# POC-save.net
KiCad netlist of a schematic drawn in EAGLE
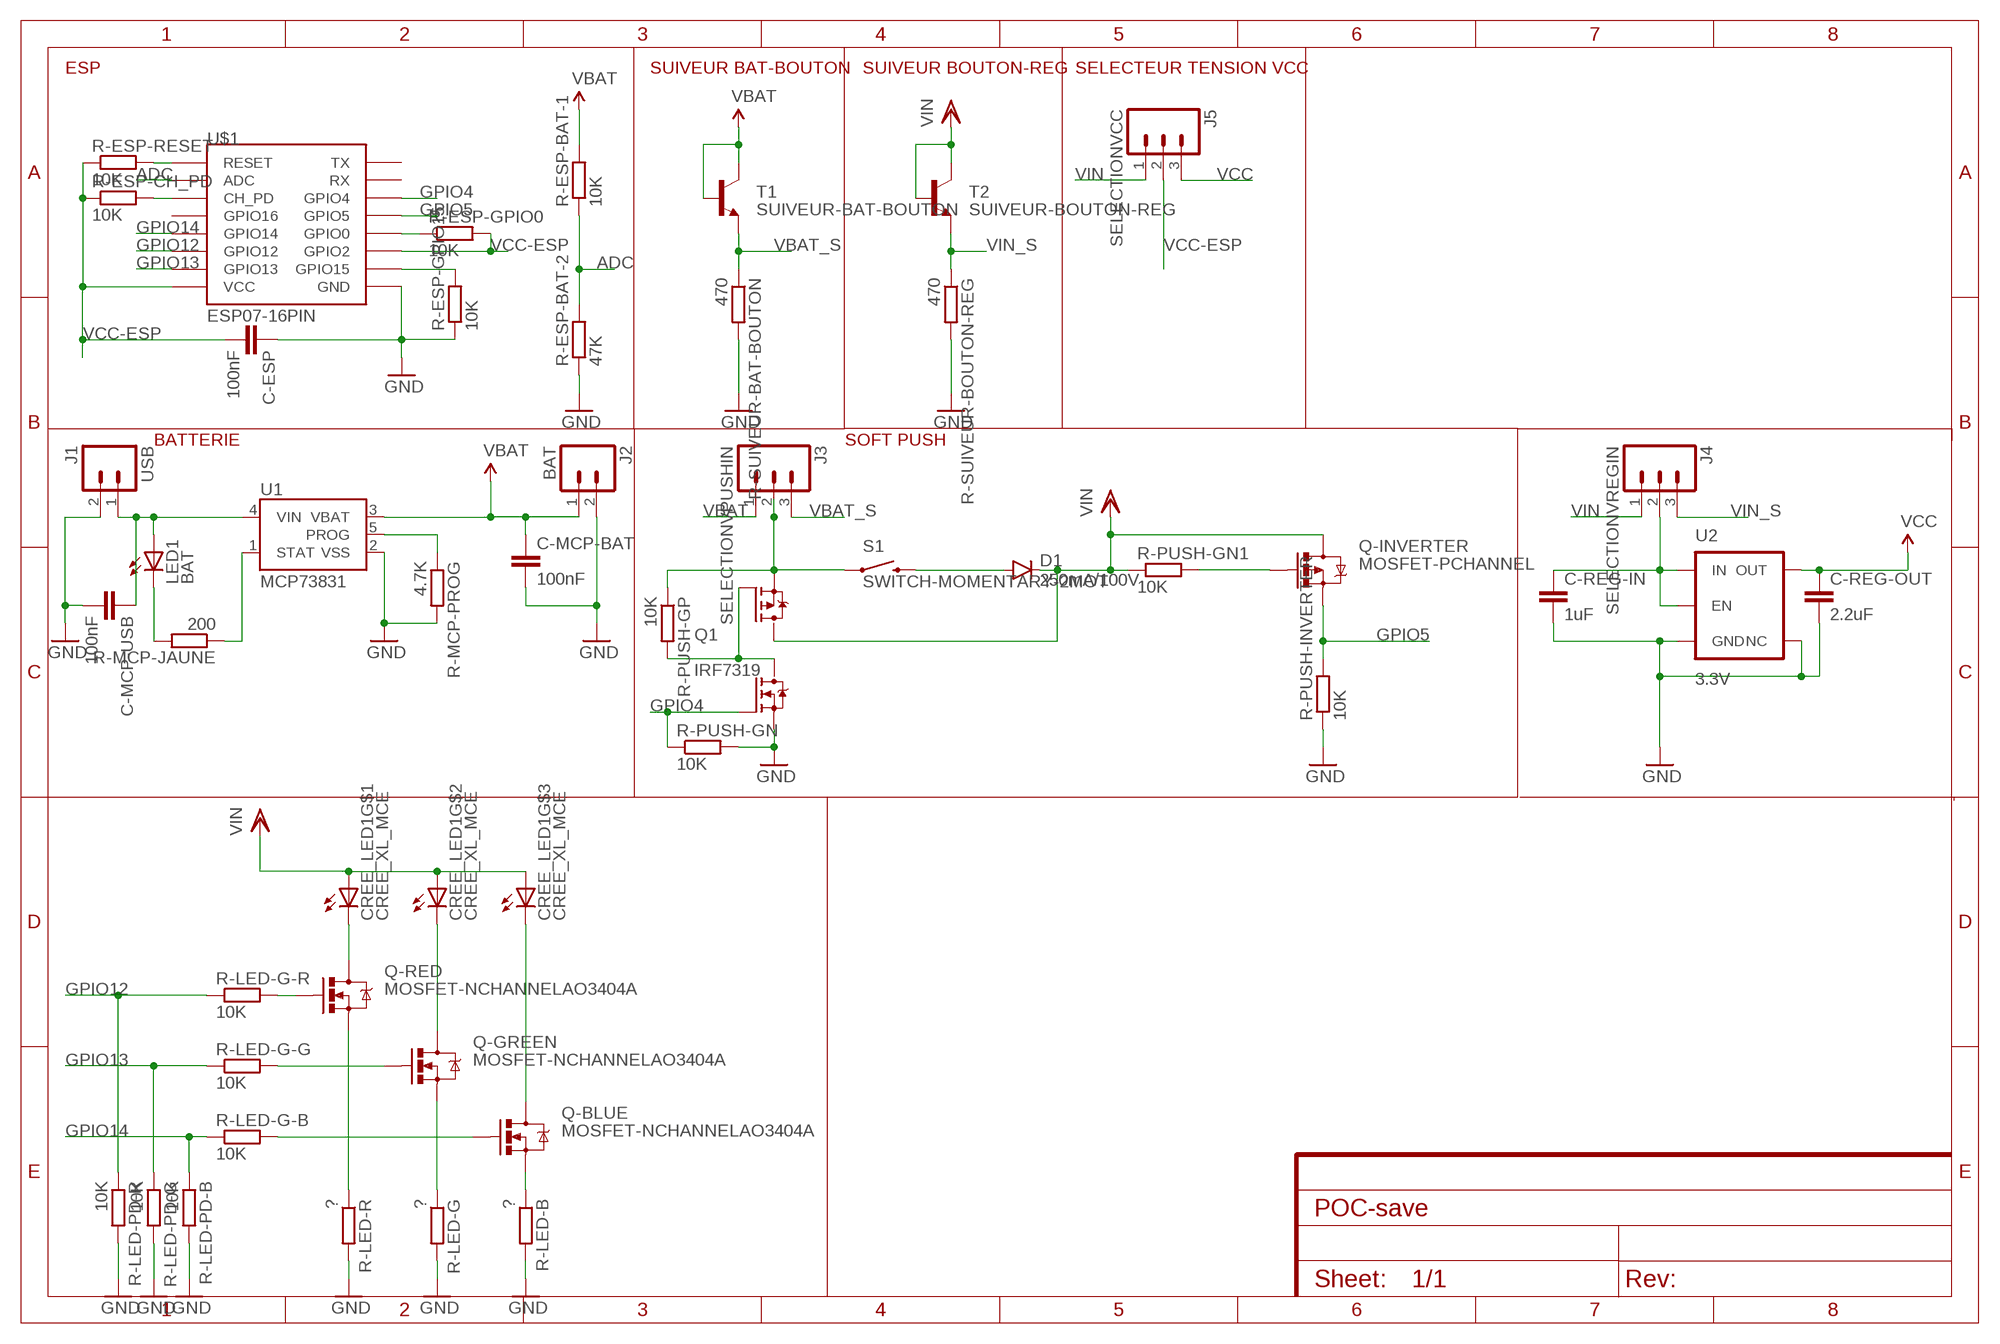
[diagram p0: schematic, sheet 1]

(export (version "E")
  (design (tool "Eeschema 10.0.6"))
  (components
    (comp (ref "C-ESP")
      (value "100nF")
      (footprint "eagle-import:C0805")
      (libsource (lib "eagle-import") (part "C-EUC0805"))
    )
    (comp (ref "C-MCP-BAT")
      (value "100nF")
      (footprint "eagle-import:C0805")
      (libsource (lib "eagle-import") (part "C-EUC0805"))
    )
    (comp (ref "C-MCP-USB")
      (value "100nF")
      (footprint "eagle-import:C0805")
      (libsource (lib "eagle-import") (part "C-EUC0805"))
    )
    (comp (ref "C-REG-IN")
      (value "1uF")
      (footprint "eagle-import:C0805")
      (libsource (lib "eagle-import") (part "C-EUC0805"))
    )
    (comp (ref "C-REG-OUT")
      (value "2.2uF")
      (footprint "eagle-import:C0805")
      (libsource (lib "eagle-import") (part "C-EUC0805"))
    )
    (comp (ref "CREE_LED1")
      (value "CREE_XL_MCE")
      (footprint "eagle-import:CREE_XL_MCE")
      (libsource (lib "eagle-import") (part "CREE_XL_MCE"))
    )
    (comp (ref "D1")
      (value "250mA/100V")
      (footprint "eagle-import:SOD-323")
      (libsource (lib "eagle-import") (part "DIODEBAS16"))
    )
    (comp (ref "J1")
      (value "USB")
      (footprint "eagle-import:1X02")
      (libsource (lib "eagle-import") (part "M02PTH"))
    )
    (comp (ref "J2")
      (value "BAT")
      (footprint "eagle-import:1X02")
      (libsource (lib "eagle-import") (part "M02PTH"))
    )
    (comp (ref "J3")
      (value "SELECTIONVPUSHIN")
      (footprint "eagle-import:1X03")
      (libsource (lib "eagle-import") (part "M03PTH"))
    )
    (comp (ref "J4")
      (value "SELECTIONVREGIN")
      (footprint "eagle-import:1X03")
      (libsource (lib "eagle-import") (part "M03PTH"))
    )
    (comp (ref "J5")
      (value "SELECTIONVCC")
      (footprint "eagle-import:1X03")
      (libsource (lib "eagle-import") (part "M03PTH"))
    )
    (comp (ref "LED1")
      (value "BAT")
      (footprint "eagle-import:CHIPLED_0805")
      (libsource (lib "eagle-import") (part "LEDCHIPLED_0805"))
    )
    (comp (ref "Q-BLUE")
      (value "MOSFET-NCHANNELAO3404A")
      (footprint "eagle-import:SOT23-3")
      (libsource (lib "eagle-import") (part "MOSFET-NCHANNELAO3404A"))
    )
    (comp (ref "Q-GREEN")
      (value "MOSFET-NCHANNELAO3404A")
      (footprint "eagle-import:SOT23-3")
      (libsource (lib "eagle-import") (part "MOSFET-NCHANNELAO3404A"))
    )
    (comp (ref "Q-INVERTER")
      (value "MOSFET-PCHANNEL")
      (footprint "eagle-import:SOT23-3")
      (libsource (lib "eagle-import") (part "MOSFET-PCHANNEL"))
    )
    (comp (ref "Q-RED")
      (value "MOSFET-NCHANNELAO3404A")
      (footprint "eagle-import:SOT23-3")
      (libsource (lib "eagle-import") (part "MOSFET-NCHANNELAO3404A"))
    )
    (comp (ref "Q1")
      (value "IRF7319")
      (footprint "eagle-import:SO08-IRF")
      (libsource (lib "eagle-import") (part "IRF7319"))
    )
    (comp (ref "R-ESP-BAT-1")
      (value "10K")
      (footprint "eagle-import:M0805")
      (libsource (lib "eagle-import") (part "R-EU_M0805"))
    )
    (comp (ref "R-ESP-BAT-2")
      (value "47K")
      (footprint "eagle-import:M0805")
      (libsource (lib "eagle-import") (part "R-EU_M0805"))
    )
    (comp (ref "R-ESP-CH_PD")
      (value "10K")
      (footprint "eagle-import:M0805")
      (libsource (lib "eagle-import") (part "R-EU_M0805"))
    )
    (comp (ref "R-ESP-GPIO0")
      (value "10K")
      (footprint "eagle-import:M0805")
      (libsource (lib "eagle-import") (part "R-EU_M0805"))
    )
    (comp (ref "R-ESP-GPIO15")
      (value "10K")
      (footprint "eagle-import:M0805")
      (libsource (lib "eagle-import") (part "R-EU_M0805"))
    )
    (comp (ref "R-ESP-RESET")
      (value "10K")
      (footprint "eagle-import:M0805")
      (libsource (lib "eagle-import") (part "R-EU_M0805"))
    )
    (comp (ref "R-LED-B")
      (value "?")
      (footprint "eagle-import:M0805")
      (libsource (lib "eagle-import") (part "R-EU_M0805"))
    )
    (comp (ref "R-LED-G")
      (value "?")
      (footprint "eagle-import:M0805")
      (libsource (lib "eagle-import") (part "R-EU_M0805"))
    )
    (comp (ref "R-LED-G-B")
      (value "10K")
      (footprint "eagle-import:M0805")
      (libsource (lib "eagle-import") (part "R-EU_M0805"))
    )
    (comp (ref "R-LED-G-G")
      (value "10K")
      (footprint "eagle-import:M0805")
      (libsource (lib "eagle-import") (part "R-EU_M0805"))
    )
    (comp (ref "R-LED-G-R")
      (value "10K")
      (footprint "eagle-import:M0805")
      (libsource (lib "eagle-import") (part "R-EU_M0805"))
    )
    (comp (ref "R-LED-PD-B")
      (value "10K")
      (footprint "eagle-import:M0805")
      (libsource (lib "eagle-import") (part "R-EU_M0805"))
    )
    (comp (ref "R-LED-PD-G")
      (value "10K")
      (footprint "eagle-import:M0805")
      (libsource (lib "eagle-import") (part "R-EU_M0805"))
    )
    (comp (ref "R-LED-PD-R")
      (value "10K")
      (footprint "eagle-import:M0805")
      (libsource (lib "eagle-import") (part "R-EU_M0805"))
    )
    (comp (ref "R-LED-R")
      (value "?")
      (footprint "eagle-import:M0805")
      (libsource (lib "eagle-import") (part "R-EU_M0805"))
    )
    (comp (ref "R-MCP-JAUNE")
      (value "200")
      (footprint "eagle-import:M0805")
      (libsource (lib "eagle-import") (part "R-EU_M0805"))
    )
    (comp (ref "R-MCP-PROG")
      (value "4.7K")
      (footprint "eagle-import:M0805")
      (libsource (lib "eagle-import") (part "R-EU_M0805"))
    )
    (comp (ref "R-PUSH-GN")
      (value "10K")
      (footprint "eagle-import:M0805")
      (libsource (lib "eagle-import") (part "R-EU_M0805"))
    )
    (comp (ref "R-PUSH-GN1")
      (value "10K")
      (footprint "eagle-import:M0805")
      (libsource (lib "eagle-import") (part "R-EU_M0805"))
    )
    (comp (ref "R-PUSH-GP")
      (value "10K")
      (footprint "eagle-import:M0805")
      (libsource (lib "eagle-import") (part "R-EU_M0805"))
    )
    (comp (ref "R-PUSH-INVERTER")
      (value "10K")
      (footprint "eagle-import:M0805")
      (libsource (lib "eagle-import") (part "R-EU_M0805"))
    )
    (comp (ref "R-SUIVEUR-BAT-BOUTON")
      (value "470")
      (footprint "eagle-import:M0805")
      (libsource (lib "eagle-import") (part "R-EU_M0805"))
    )
    (comp (ref "R-SUIVEUR-BOUTON-REG")
      (value "470")
      (footprint "eagle-import:M0805")
      (libsource (lib "eagle-import") (part "R-EU_M0805"))
    )
    (comp (ref "S1")
      (value "SWITCH-MOMENTARY-2MOT")
      (footprint "eagle-import:TACTILE-PTH")
      (libsource (lib "eagle-import") (part "SWITCH-MOMENTARY-2MOT"))
    )
    (comp (ref "T1")
      (value "SUIVEUR-BAT-BOUTON")
      (footprint "eagle-import:SOT23-3")
      (libsource (lib "eagle-import") (part "TRANSISTOR_NPNSOT23-3"))
    )
    (comp (ref "T2")
      (value "SUIVEUR-BOUTON-REG")
      (footprint "eagle-import:SOT23-3")
      (libsource (lib "eagle-import") (part "TRANSISTOR_NPNSOT23-3"))
    )
    (comp (ref "U$1")
      (value "ESP07-16PIN")
      (footprint "eagle-import:ESP07-16PIN")
      (libsource (lib "eagle-import") (part "ESP07-16PIN"))
    )
    (comp (ref "U1")
      (value "MCP73831")
      (footprint "eagle-import:SOT23-5")
      (libsource (lib "eagle-import") (part "MCP73831"))
    )
    (comp (ref "U2")
      (value "3.3V")
      (footprint "eagle-import:SOT23-5")
      (libsource (lib "eagle-import") (part "V_REG_AP2112K-3.3V"))
    )
  )
  (nets
    (net (code "1") (name "/ADC") (class "Default")
      (node (ref "R-ESP-BAT-1") (pin "1") (pinfunction "1_1") (pintype "passive"))
      (node (ref "R-ESP-BAT-2") (pin "2") (pinfunction "2_2") (pintype "passive"))
      (node (ref "U$1") (pin "ADC") (pinfunction "ADC_ADC") (pintype "bidirectional"))
    )
    (net (code "2") (name "/GPIO4") (class "Default")
      (node (ref "Q1") (pin "2") (pinfunction "N-G_2") (pintype "passive"))
      (node (ref "R-PUSH-GN") (pin "1") (pinfunction "1_1") (pintype "passive"))
      (node (ref "U$1") (pin "GPIO4") (pinfunction "GPIO4_GPIO4") (pintype "bidirectional"))
    )
    (net (code "3") (name "/GPIO5") (class "Default")
      (node (ref "Q-INVERTER") (pin "2") (pinfunction "S_2") (pintype "passive"))
      (node (ref "R-PUSH-INVERTER") (pin "2") (pinfunction "2_2") (pintype "passive"))
      (node (ref "U$1") (pin "GPIO5") (pinfunction "GPIO5_GPIO5") (pintype "bidirectional"))
    )
    (net (code "4") (name "/GPIO12") (class "Default")
      (node (ref "R-LED-G-R") (pin "1") (pinfunction "1_1") (pintype "passive"))
      (node (ref "R-LED-PD-R") (pin "1") (pinfunction "1_1") (pintype "passive"))
      (node (ref "U$1") (pin "GPIO12") (pinfunction "GPIO12_GPIO12") (pintype "bidirectional"))
    )
    (net (code "5") (name "/GPIO13") (class "Default")
      (node (ref "R-LED-G-G") (pin "1") (pinfunction "1_1") (pintype "passive"))
      (node (ref "R-LED-PD-G") (pin "1") (pinfunction "1_1") (pintype "passive"))
      (node (ref "U$1") (pin "GPIO13") (pinfunction "GPIO13_GPIO13") (pintype "bidirectional"))
    )
    (net (code "6") (name "/GPIO14") (class "Default")
      (node (ref "R-LED-G-B") (pin "1") (pinfunction "1_1") (pintype "passive"))
      (node (ref "R-LED-PD-B") (pin "1") (pinfunction "1_1") (pintype "passive"))
      (node (ref "U$1") (pin "GPIO14") (pinfunction "GPIO14_GPIO14") (pintype "bidirectional"))
    )
    (net (code "7") (name "/VBAT_S") (class "Default")
      (node (ref "J3") (pin "3") (pinfunction "3_3") (pintype "passive"))
      (node (ref "R-SUIVEUR-BAT-BOUTON") (pin "1") (pinfunction "1_1") (pintype "passive"))
      (node (ref "T1") (pin "2") (pinfunction "E_2") (pintype "passive"))
    )
    (net (code "8") (name "/VCC-ESP") (class "Default")
      (node (ref "C-ESP") (pin "2") (pinfunction "2_2") (pintype "passive"))
      (node (ref "J5") (pin "2") (pinfunction "2_2") (pintype "passive"))
      (node (ref "R-ESP-CH_PD") (pin "1") (pinfunction "1_1") (pintype "passive"))
      (node (ref "R-ESP-GPIO0") (pin "2") (pinfunction "2_2") (pintype "passive"))
      (node (ref "R-ESP-RESET") (pin "1") (pinfunction "1_1") (pintype "passive"))
      (node (ref "U$1") (pin "GPIO2") (pinfunction "GPIO2_GPIO2") (pintype "bidirectional"))
      (node (ref "U$1") (pin "VCC") (pinfunction "VCC_VCC") (pintype "bidirectional"))
    )
    (net (code "9") (name "/VIN_S") (class "Default")
      (node (ref "J4") (pin "3") (pinfunction "3_3") (pintype "passive"))
      (node (ref "R-SUIVEUR-BOUTON-REG") (pin "1") (pinfunction "1_1") (pintype "passive"))
      (node (ref "T2") (pin "2") (pinfunction "E_2") (pintype "passive"))
    )
    (net (code "10") (name "GND") (class "Default")
      (node (ref "C-ESP") (pin "1") (pinfunction "1_1") (pintype "passive"))
      (node (ref "C-MCP-BAT") (pin "2") (pinfunction "2_2") (pintype "passive"))
      (node (ref "C-MCP-USB") (pin "2") (pinfunction "2_2") (pintype "passive"))
      (node (ref "C-REG-IN") (pin "2") (pinfunction "2_2") (pintype "passive"))
      (node (ref "C-REG-OUT") (pin "2") (pinfunction "2_2") (pintype "passive"))
      (node (ref "J1") (pin "2") (pinfunction "2_2") (pintype "passive"))
      (node (ref "J2") (pin "2") (pinfunction "2_2") (pintype "passive"))
      (node (ref "Q1") (pin "1") (pinfunction "N-S_1") (pintype "passive"))
      (node (ref "R-ESP-BAT-2") (pin "1") (pinfunction "1_1") (pintype "passive"))
      (node (ref "R-ESP-GPIO15") (pin "1") (pinfunction "1_1") (pintype "passive"))
      (node (ref "R-LED-B") (pin "2") (pinfunction "2_2") (pintype "passive"))
      (node (ref "R-LED-G") (pin "2") (pinfunction "2_2") (pintype "passive"))
      (node (ref "R-LED-PD-B") (pin "2") (pinfunction "2_2") (pintype "passive"))
      (node (ref "R-LED-PD-G") (pin "2") (pinfunction "2_2") (pintype "passive"))
      (node (ref "R-LED-PD-R") (pin "2") (pinfunction "2_2") (pintype "passive"))
      (node (ref "R-LED-R") (pin "2") (pinfunction "2_2") (pintype "passive"))
      (node (ref "R-MCP-PROG") (pin "2") (pinfunction "2_2") (pintype "passive"))
      (node (ref "R-PUSH-GN") (pin "2") (pinfunction "2_2") (pintype "passive"))
      (node (ref "R-PUSH-INVERTER") (pin "1") (pinfunction "1_1") (pintype "passive"))
      (node (ref "R-SUIVEUR-BAT-BOUTON") (pin "2") (pinfunction "2_2") (pintype "passive"))
      (node (ref "R-SUIVEUR-BOUTON-REG") (pin "2") (pinfunction "2_2") (pintype "passive"))
      (node (ref "U$1") (pin "GND") (pinfunction "GND_GND") (pintype "bidirectional"))
      (node (ref "U1") (pin "2") (pinfunction "VSS_2") (pintype "power_in"))
      (node (ref "U2") (pin "2") (pinfunction "GND_2") (pintype "input"))
      (node (ref "U2") (pin "4") (pinfunction "NC_4") (pintype "input"))
    )
    (net (code "11") (name "Net-(CREE_LED1A-C)") (class "Default")
      (node (ref "CREE_LED1") (pin "8") (pinfunction "C_8") (pintype "passive"))
      (node (ref "Q-RED") (pin "3") (pinfunction "D_3") (pintype "passive"))
    )
    (net (code "12") (name "Net-(CREE_LED1B-C)") (class "Default")
      (node (ref "CREE_LED1") (pin "7") (pinfunction "C_7") (pintype "passive"))
      (node (ref "Q-GREEN") (pin "3") (pinfunction "D_3") (pintype "passive"))
    )
    (net (code "13") (name "Net-(CREE_LED1C-C)") (class "Default")
      (node (ref "CREE_LED1") (pin "6") (pinfunction "C_6") (pintype "passive"))
      (node (ref "Q-BLUE") (pin "3") (pinfunction "D_3") (pintype "passive"))
    )
    (net (code "14") (name "Net-(LED1-PadC)") (class "Default")
      (node (ref "LED1") (pin "C") (pinfunction "C_C") (pintype "passive"))
      (node (ref "R-MCP-JAUNE") (pin "2") (pinfunction "2_2") (pintype "passive"))
    )
    (net (code "15") (name "Net-(Q-BLUE-G)") (class "Default")
      (node (ref "Q-BLUE") (pin "1") (pinfunction "G_1") (pintype "passive"))
      (node (ref "R-LED-G-B") (pin "2") (pinfunction "2_2") (pintype "passive"))
    )
    (net (code "16") (name "Net-(Q-BLUE-S)") (class "Default")
      (node (ref "Q-BLUE") (pin "2") (pinfunction "S_2") (pintype "passive"))
      (node (ref "R-LED-B") (pin "1") (pinfunction "1_1") (pintype "passive"))
    )
    (net (code "17") (name "Net-(Q-GREEN-G)") (class "Default")
      (node (ref "Q-GREEN") (pin "1") (pinfunction "G_1") (pintype "passive"))
      (node (ref "R-LED-G-G") (pin "2") (pinfunction "2_2") (pintype "passive"))
    )
    (net (code "18") (name "Net-(Q-GREEN-S)") (class "Default")
      (node (ref "Q-GREEN") (pin "2") (pinfunction "S_2") (pintype "passive"))
      (node (ref "R-LED-G") (pin "1") (pinfunction "1_1") (pintype "passive"))
    )
    (net (code "19") (name "Net-(Q-INVERTER-G)") (class "Default")
      (node (ref "Q-INVERTER") (pin "1") (pinfunction "G_1") (pintype "passive"))
      (node (ref "R-PUSH-GN1") (pin "2") (pinfunction "2_2") (pintype "passive"))
    )
    (net (code "20") (name "Net-(Q-RED-G)") (class "Default")
      (node (ref "Q-RED") (pin "1") (pinfunction "G_1") (pintype "passive"))
      (node (ref "R-LED-G-R") (pin "2") (pinfunction "2_2") (pintype "passive"))
    )
    (net (code "21") (name "Net-(Q-RED-S)") (class "Default")
      (node (ref "Q-RED") (pin "2") (pinfunction "S_2") (pintype "passive"))
      (node (ref "R-LED-R") (pin "1") (pinfunction "1_1") (pintype "passive"))
    )
    (net (code "22") (name "Net-(Q1-P-G)") (class "Default")
      (node (ref "Q1") (pin "4") (pinfunction "P-G_4") (pintype "passive"))
      (node (ref "Q1") (pin "7") (pinfunction "N-D_7") (pintype "passive"))
      (node (ref "Q1") (pin "8") (pinfunction "N-D_8") (pintype "passive"))
      (node (ref "R-PUSH-GP") (pin "2") (pinfunction "2_2") (pintype "passive"))
    )
    (net (code "23") (name "Net-(Q1-P-S)") (class "Default")
      (node (ref "J3") (pin "2") (pinfunction "2_2") (pintype "passive"))
      (node (ref "Q1") (pin "3") (pinfunction "P-S_3") (pintype "passive"))
      (node (ref "R-PUSH-GP") (pin "1") (pinfunction "1_1") (pintype "passive"))
      (node (ref "S1") (pin "1") (pinfunction "1_1") (pintype "passive"))
    )
    (net (code "24") (name "Net-(R-ESP-CH_PD-Pad2)") (class "Default")
      (node (ref "R-ESP-CH_PD") (pin "2") (pinfunction "2_2") (pintype "passive"))
      (node (ref "U$1") (pin "CH_PD") (pinfunction "CH_PD_CH_PD") (pintype "bidirectional"))
    )
    (net (code "25") (name "Net-(R-ESP-GPIO0-Pad1)") (class "Default")
      (node (ref "R-ESP-GPIO0") (pin "1") (pinfunction "1_1") (pintype "passive"))
      (node (ref "U$1") (pin "GPIO0") (pinfunction "GPIO0_GPIO0") (pintype "bidirectional"))
    )
    (net (code "26") (name "Net-(R-ESP-GPIO15-Pad2)") (class "Default")
      (node (ref "R-ESP-GPIO15") (pin "2") (pinfunction "2_2") (pintype "passive"))
      (node (ref "U$1") (pin "GPIO15") (pinfunction "GPIO15_GPIO15") (pintype "bidirectional"))
    )
    (net (code "27") (name "Net-(S1-2)") (class "Default")
      (node (ref "D1") (pin "A") (pinfunction "A_A") (pintype "passive"))
      (node (ref "S1") (pin "4") (pinfunction "2_4") (pintype "passive"))
    )
    (net (code "28") (name "Net-(U$1-RESET)") (class "Default")
      (node (ref "R-ESP-RESET") (pin "2") (pinfunction "2_2") (pintype "passive"))
      (node (ref "U$1") (pin "REST") (pinfunction "RESET_REST") (pintype "bidirectional"))
    )
    (net (code "29") (name "Net-(U1-PROG)") (class "Default")
      (node (ref "R-MCP-PROG") (pin "1") (pinfunction "1_1") (pintype "passive"))
      (node (ref "U1") (pin "5") (pinfunction "PROG_5") (pintype "input"))
    )
    (net (code "30") (name "Net-(U1-STAT)") (class "Default")
      (node (ref "R-MCP-JAUNE") (pin "1") (pinfunction "1_1") (pintype "passive"))
      (node (ref "U1") (pin "1") (pinfunction "STAT_1") (pintype "output"))
    )
    (net (code "31") (name "Net-(U1-VIN)") (class "Default")
      (node (ref "C-MCP-USB") (pin "1") (pinfunction "1_1") (pintype "passive"))
      (node (ref "J1") (pin "1") (pinfunction "1_1") (pintype "passive"))
      (node (ref "LED1") (pin "A") (pinfunction "A_A") (pintype "passive"))
      (node (ref "U1") (pin "4") (pinfunction "VIN_4") (pintype "power_in"))
    )
    (net (code "32") (name "Net-(U2-EN)") (class "Default")
      (node (ref "C-REG-IN") (pin "1") (pinfunction "1_1") (pintype "passive"))
      (node (ref "J4") (pin "2") (pinfunction "2_2") (pintype "passive"))
      (node (ref "U2") (pin "1") (pinfunction "IN_1") (pintype "input"))
      (node (ref "U2") (pin "3") (pinfunction "EN_3") (pintype "input"))
    )
    (net (code "33") (name "VBAT") (class "Default")
      (node (ref "C-MCP-BAT") (pin "1") (pinfunction "1_1") (pintype "passive"))
      (node (ref "J2") (pin "1") (pinfunction "1_1") (pintype "passive"))
      (node (ref "J3") (pin "1") (pinfunction "1_1") (pintype "passive"))
      (node (ref "R-ESP-BAT-1") (pin "2") (pinfunction "2_2") (pintype "passive"))
      (node (ref "T1") (pin "1") (pinfunction "B_1") (pintype "passive"))
      (node (ref "T1") (pin "3") (pinfunction "C_3") (pintype "passive"))
      (node (ref "U1") (pin "3") (pinfunction "VBAT_3") (pintype "power_in"))
    )
    (net (code "34") (name "VCC") (class "Default")
      (node (ref "C-REG-OUT") (pin "1") (pinfunction "1_1") (pintype "passive"))
      (node (ref "J5") (pin "3") (pinfunction "3_3") (pintype "passive"))
      (node (ref "U2") (pin "5") (pinfunction "OUT_5") (pintype "passive"))
    )
    (net (code "35") (name "VIN") (class "Default")
      (node (ref "CREE_LED1") (pin "1") (pinfunction "A_1") (pintype "passive"))
      (node (ref "CREE_LED1") (pin "2") (pinfunction "A_2") (pintype "passive"))
      (node (ref "CREE_LED1") (pin "3") (pinfunction "A_3") (pintype "passive"))
      (node (ref "D1") (pin "C") (pinfunction "C_C") (pintype "passive"))
      (node (ref "J4") (pin "1") (pinfunction "1_1") (pintype "passive"))
      (node (ref "J5") (pin "1") (pinfunction "1_1") (pintype "passive"))
      (node (ref "Q-INVERTER") (pin "3") (pinfunction "D_3") (pintype "passive"))
      (node (ref "Q1") (pin "5") (pinfunction "P-D_5") (pintype "passive"))
      (node (ref "Q1") (pin "6") (pinfunction "P-D_6") (pintype "passive"))
      (node (ref "R-PUSH-GN1") (pin "1") (pinfunction "1_1") (pintype "passive"))
      (node (ref "T2") (pin "1") (pinfunction "B_1") (pintype "passive"))
      (node (ref "T2") (pin "3") (pinfunction "C_3") (pintype "passive"))
    )
    (net (code "36") (name "unconnected-(U$1-PadGPIO16)") (class "Default")
      (node (ref "U$1") (pin "GPIO16") (pinfunction "GPIO16_GPIO16") (pintype "bidirectional"))
    )
    (net (code "37") (name "unconnected-(U$1-PadRX)") (class "Default")
      (node (ref "U$1") (pin "RX") (pinfunction "RX_RX") (pintype "bidirectional"))
    )
    (net (code "38") (name "unconnected-(U$1-PadTX)") (class "Default")
      (node (ref "U$1") (pin "TX") (pinfunction "TX_TX") (pintype "bidirectional"))
    )
  )
)
